# SController-8833.net
KiCad netlist of a schematic drawn in EAGLE
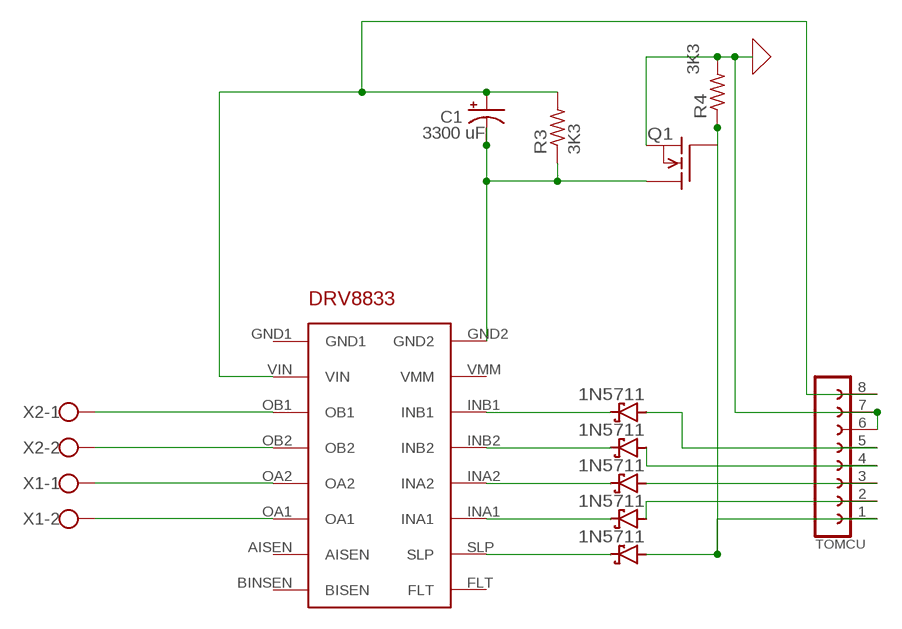
[diagram p0: schematic, sheet 1]

(export (version "E")
  (design (tool "Eeschema 10.0.6"))
  (components
    (comp (ref "\"\"")
      (value "POLOLU-DRV8833")
      (footprint "eagle-import:POLOLU-DRV8833")
      (libsource (lib "eagle-import") (part "POLOLU-DRV8833"))
    )
    (comp (ref "C1")
      (value "3300 uF")
      (footprint "eagle-import:E5-10,5")
      (libsource (lib "eagle-import") (part "CPOL-USE5-10.5"))
    )
    (comp (ref "D1")
      (value "1N5711")
      (footprint "eagle-import:F126Z12")
      (libsource (lib "eagle-import") (part "SCHOTTKY-DIODEF126Z12"))
    )
    (comp (ref "D2")
      (value "1N5711")
      (footprint "eagle-import:F126Z12")
      (libsource (lib "eagle-import") (part "SCHOTTKY-DIODEF126Z12"))
    )
    (comp (ref "D3")
      (value "1N5711")
      (footprint "eagle-import:F126Z12")
      (libsource (lib "eagle-import") (part "SCHOTTKY-DIODEF126Z12"))
    )
    (comp (ref "D4")
      (value "1N5711")
      (footprint "eagle-import:F126Z12")
      (libsource (lib "eagle-import") (part "SCHOTTKY-DIODEF126Z12"))
    )
    (comp (ref "D5")
      (value "1N5711")
      (footprint "eagle-import:F126Z12")
      (libsource (lib "eagle-import") (part "SCHOTTKY-DIODEF126Z12"))
    )
    (comp (ref "Q1")
      (value "SUP75N06-08")
      (footprint "eagle-import:TO220")
      (libsource (lib "eagle-import") (part "SUP75N06-08"))
    )
    (comp (ref "R3")
      (value "3K3")
      (footprint "eagle-import:0204_7")
      (libsource (lib "eagle-import") (part "R-US_0204/7"))
    )
    (comp (ref "R4")
      (value "R-US_0204/7")
      (footprint "eagle-import:0204_7")
      (fields (field (name "SPICEPREFIX") "R") (field (name "SPICEPREFIX_1") "3K3"))
      (libsource (lib "eagle-import") (part "R-US_0204/7"))
    )
    (comp (ref "TOMCU")
      (value "FE08-1")
      (footprint "eagle-import:FE08")
      (libsource (lib "eagle-import") (part "FE08-1"))
    )
    (comp (ref "X1")
      (value "W237-102")
      (footprint "eagle-import:W237-102")
      (fields (field (name "MPN") "237-102"))
      (libsource (lib "eagle-import") (part "W237-102"))
    )
    (comp (ref "X2")
      (value "W237-102")
      (footprint "eagle-import:W237-102")
      (fields (field (name "MPN") "237-102"))
      (libsource (lib "eagle-import") (part "W237-102"))
    )
  )
  (nets
    (net (code "1") (name "GND") (class "Default")
      (node (ref "Q1") (pin "3") (pinfunction "S_3") (pintype "passive"))
      (node (ref "R4") (pin "2") (pinfunction "2_2") (pintype "passive"))
      (node (ref "TOMCU") (pin "6") (pinfunction "6_6") (pintype "passive"))
      (node (ref "TOMCU") (pin "7") (pinfunction "7_7") (pintype "passive"))
    )
    (net (code "2") (name "Net-(\"\"-PadINA1)") (class "Default")
      (node (ref "\"\"") (pin "INA1") (pinfunction "INA1_INA1") (pintype "bidirectional"))
      (node (ref "D5") (pin "C") (pinfunction "C_C") (pintype "passive"))
    )
    (net (code "3") (name "Net-(\"\"-PadINA2)") (class "Default")
      (node (ref "\"\"") (pin "INA2") (pinfunction "INA2_INA2") (pintype "bidirectional"))
      (node (ref "D4") (pin "C") (pinfunction "C_C") (pintype "passive"))
    )
    (net (code "4") (name "Net-(\"\"-PadINB1)") (class "Default")
      (node (ref "\"\"") (pin "INB1") (pinfunction "INB1_INB1") (pintype "bidirectional"))
      (node (ref "D1") (pin "C") (pinfunction "C_C") (pintype "passive"))
    )
    (net (code "5") (name "Net-(\"\"-PadINB2)") (class "Default")
      (node (ref "\"\"") (pin "INB2") (pinfunction "INB2_INB2") (pintype "bidirectional"))
      (node (ref "D2") (pin "C") (pinfunction "C_C") (pintype "passive"))
    )
    (net (code "6") (name "Net-(\"\"-PadSLP)") (class "Default")
      (node (ref "\"\"") (pin "SLP") (pinfunction "SLP_SLP") (pintype "bidirectional"))
      (node (ref "D3") (pin "C") (pinfunction "C_C") (pintype "passive"))
    )
    (net (code "7") (name "Net-(\"\"-PadVIN)") (class "Default")
      (node (ref "\"\"") (pin "VIN") (pinfunction "VIN_VIN") (pintype "bidirectional"))
      (node (ref "C1") (pin "+") (pinfunction "+_+") (pintype "passive"))
      (node (ref "R3") (pin "2") (pinfunction "2_2") (pintype "passive"))
      (node (ref "TOMCU") (pin "8") (pinfunction "8_8") (pintype "passive"))
    )
    (net (code "8") (name "Net-(D1-PadA)") (class "Default")
      (node (ref "D1") (pin "A") (pinfunction "A_A") (pintype "passive"))
      (node (ref "TOMCU") (pin "5") (pinfunction "5_5") (pintype "passive"))
    )
    (net (code "9") (name "Net-(D2-PadA)") (class "Default")
      (node (ref "D2") (pin "A") (pinfunction "A_A") (pintype "passive"))
      (node (ref "TOMCU") (pin "4") (pinfunction "4_4") (pintype "passive"))
    )
    (net (code "10") (name "Net-(D4-PadA)") (class "Default")
      (node (ref "D4") (pin "A") (pinfunction "A_A") (pintype "passive"))
      (node (ref "TOMCU") (pin "3") (pinfunction "3_3") (pintype "passive"))
    )
    (net (code "11") (name "Net-(D5-PadA)") (class "Default")
      (node (ref "D5") (pin "A") (pinfunction "A_A") (pintype "passive"))
      (node (ref "TOMCU") (pin "2") (pinfunction "2_2") (pintype "passive"))
    )
    (net (code "12") (name "Net-(Q1-D)") (class "Default")
      (node (ref "\"\"") (pin "GND2") (pinfunction "GND2_GND2") (pintype "bidirectional"))
      (node (ref "C1") (pin "-") (pinfunction "-_-") (pintype "passive"))
      (node (ref "Q1") (pin "2") (pinfunction "D_2") (pintype "passive"))
      (node (ref "R3") (pin "1") (pinfunction "1_1") (pintype "passive"))
    )
    (net (code "13") (name "Net-(Q1-G)") (class "Default")
      (node (ref "D3") (pin "A") (pinfunction "A_A") (pintype "passive"))
      (node (ref "Q1") (pin "1") (pinfunction "G_1") (pintype "passive"))
      (node (ref "R4") (pin "1") (pinfunction "1_1") (pintype "passive"))
      (node (ref "TOMCU") (pin "1") (pinfunction "1_1") (pintype "passive"))
    )
    (net (code "14") (name "Net-(X1A-KL)") (class "Default")
      (node (ref "\"\"") (pin "OA2") (pinfunction "OA2_OA2") (pintype "bidirectional"))
      (node (ref "X1") (pin "1") (pinfunction "KL_1") (pintype "passive"))
    )
    (net (code "15") (name "Net-(X1B-KL)") (class "Default")
      (node (ref "\"\"") (pin "OA1") (pinfunction "OA1_OA1") (pintype "bidirectional"))
      (node (ref "X1") (pin "2") (pinfunction "KL_2") (pintype "passive"))
    )
    (net (code "16") (name "Net-(X2A-KL)") (class "Default")
      (node (ref "\"\"") (pin "OB1") (pinfunction "OB1_OB1") (pintype "bidirectional"))
      (node (ref "X2") (pin "1") (pinfunction "KL_1") (pintype "passive"))
    )
    (net (code "17") (name "Net-(X2B-KL)") (class "Default")
      (node (ref "\"\"") (pin "OB2") (pinfunction "OB2_OB2") (pintype "bidirectional"))
      (node (ref "X2") (pin "2") (pinfunction "KL_2") (pintype "passive"))
    )
    (net (code "18") (name "unconnected-(\"\"-BISEN-PadBINSEN)") (class "Default")
      (node (ref "\"\"") (pin "BINSEN") (pinfunction "BISEN_BINSEN") (pintype "bidirectional"))
    )
    (net (code "19") (name "unconnected-(\"\"-PadAISEN)") (class "Default")
      (node (ref "\"\"") (pin "AISEN") (pinfunction "AISEN_AISEN") (pintype "bidirectional"))
    )
    (net (code "20") (name "unconnected-(\"\"-PadFLT)") (class "Default")
      (node (ref "\"\"") (pin "FLT") (pinfunction "FLT_FLT") (pintype "bidirectional"))
    )
    (net (code "21") (name "unconnected-(\"\"-PadGND1)") (class "Default")
      (node (ref "\"\"") (pin "GND1") (pinfunction "GND1_GND1") (pintype "bidirectional"))
    )
    (net (code "22") (name "unconnected-(\"\"-PadVMM)") (class "Default")
      (node (ref "\"\"") (pin "VMM") (pinfunction "VMM_VMM") (pintype "output"))
    )
  )
)
